# QTPY_v3.net
KiCad netlist of a schematic drawn in EAGLE
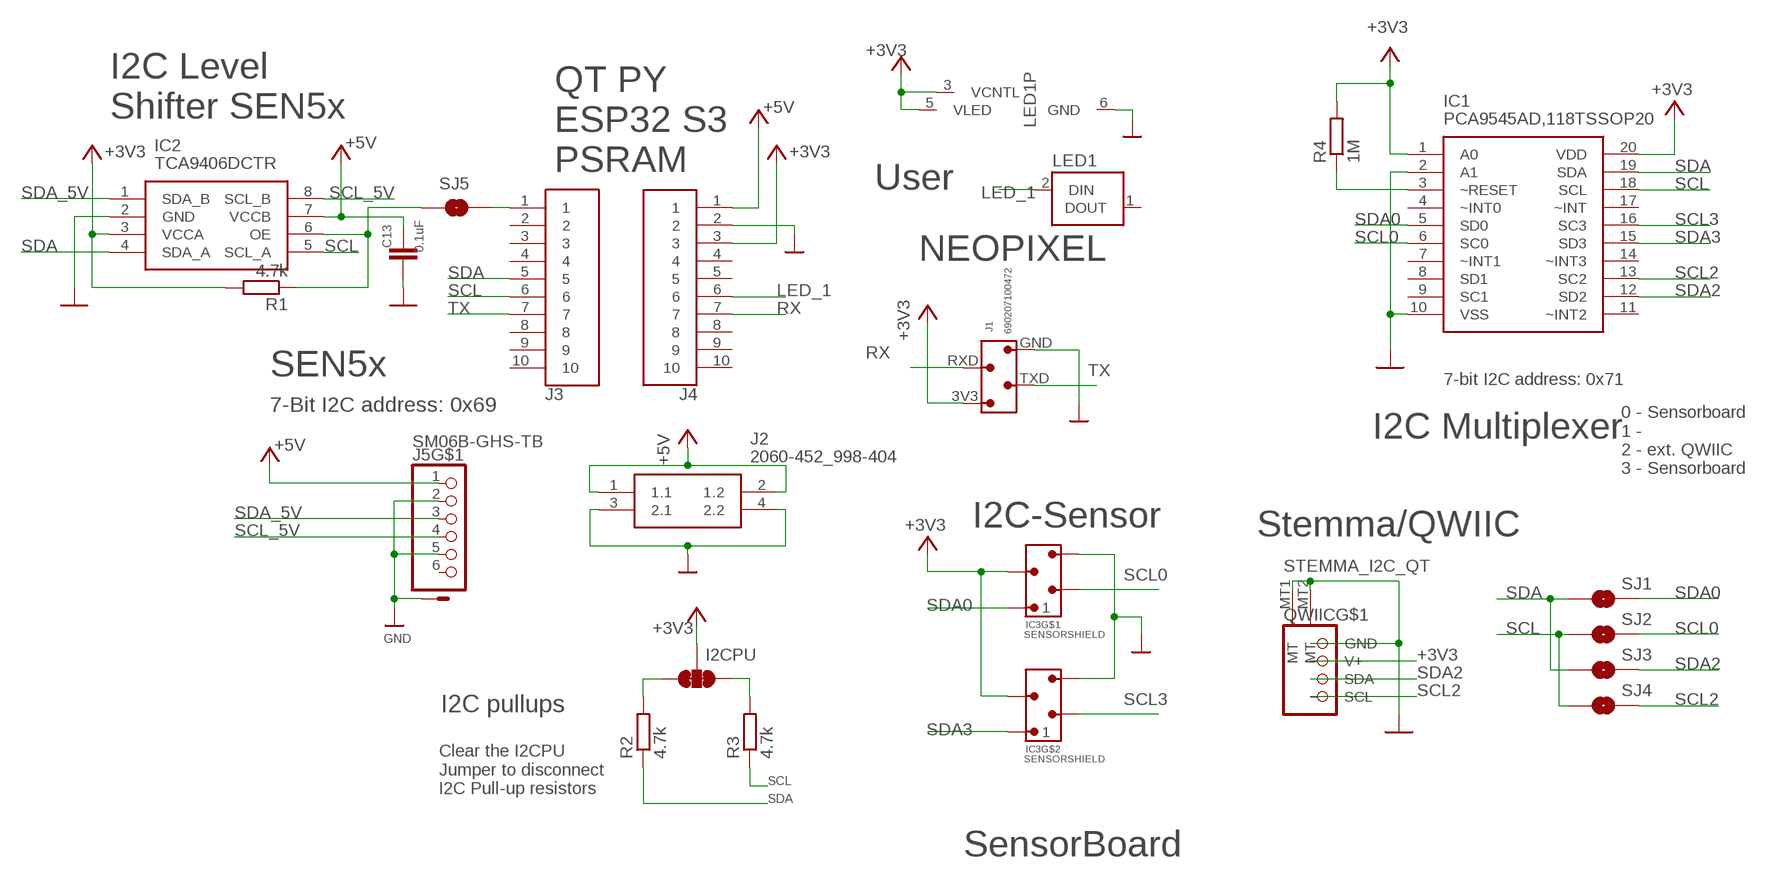
[diagram p0: schematic, sheet 1]

(export (version "E")
  (design (tool "Eeschema 10.0.6"))
  (components
    (comp (ref "C13")
      (value "0.1uF")
      (footprint "eagle-import:C0603")
      (libsource (lib "eagle-import") (part "C-EUC0603"))
    )
    (comp (ref "I2CPU")
      (value "I2C PU")
      (footprint "eagle-import:SMT-JUMPER_3_2-NC_TRACE_SILK")
      (libsource (lib "eagle-import") (part "JUMPER-SMT_3_2-NC_TRACE_SILK"))
    )
    (comp (ref "IC1")
      (value "PCA9545AD,118TSSOP20")
      (footprint "eagle-import:TSSOP20")
      (libsource (lib "eagle-import") (part "PCA9545AD,118TSSOP20"))
    )
    (comp (ref "IC2")
      (value "TCA9406DCTR")
      (footprint "eagle-import:SOP65P400X130-8N")
      (fields (field (name "MOUSER_PART_NUMBER") "595-TCA9406DCTR"))
      (libsource (lib "eagle-import") (part "TCA9406DCTR"))
    )
    (comp (ref "IC3")
      (value "SENSORSHIELD")
      (footprint "eagle-import:SENSORSHIELD")
      (libsource (lib "eagle-import") (part "SENSORSHIELD"))
    )
    (comp (ref "J1")
      (value "690207100472")
      (footprint "eagle-import:LORASHIELD")
      (libsource (lib "eagle-import") (part "LORASHIELD"))
    )
    (comp (ref "J2")
      (value "2060-452_998-404")
      (footprint "eagle-import:2060452998404")
      (fields (field (name "ARROW_PART_NUMBER") "2060-452/998-404"))
      (libsource (lib "eagle-import") (part "2060-452_998-404"))
    )
    (comp (ref "J3")
      (value "BG125-10-A-1-1-0440-N-D")
      (footprint "eagle-import:BG12510A110440ND")
      (fields (field (name "MOUSER_PART_NUMBER") "640-BG12510A110440ND"))
      (libsource (lib "eagle-import") (part "BG125-10-A-1-1-0440-N-D"))
    )
    (comp (ref "J4")
      (value "BG125-10-A-1-1-0440-N-D")
      (footprint "eagle-import:BG12510A110440ND")
      (fields (field (name "MOUSER_PART_NUMBER") "640-BG12510A110440ND"))
      (libsource (lib "eagle-import") (part "BG125-10-A-1-1-0440-N-D"))
    )
    (comp (ref "J5")
      (value "SM06B-GHS-TB")
      (footprint "eagle-import:JST-PH-06-SMD")
      (libsource (lib "eagle-import") (part "JST-PH-06-SMDSMD"))
    )
    (comp (ref "LED1")
      (value "WS2812WS2812")
      (footprint "eagle-import:WS2812")
      (libsource (lib "eagle-import") (part "WS2812WS2812"))
    )
    (comp (ref "QWIIC")
      (value "STEMMA_I2C_QT")
      (footprint "eagle-import:JST_SH4")
      (libsource (lib "eagle-import") (part "STEMMA_I2C_QT"))
    )
    (comp (ref "R1")
      (value "4.7k")
      (footprint "eagle-import:R0603")
      (libsource (lib "eagle-import") (part "R-EU_R0603"))
    )
    (comp (ref "R2")
      (value "4.7k")
      (footprint "eagle-import:R0603")
      (libsource (lib "eagle-import") (part "R-EU_R0603"))
    )
    (comp (ref "R3")
      (value "4.7k")
      (footprint "eagle-import:R0603")
      (libsource (lib "eagle-import") (part "R-EU_R0603"))
    )
    (comp (ref "R4")
      (value "1M")
      (footprint "eagle-import:R0603")
      (libsource (lib "eagle-import") (part "R-EU_R0603"))
    )
    (comp (ref "SJ1")
      (value "SOLDERJUMPERNO")
      (footprint "eagle-import:SJ_2S-NO")
      (libsource (lib "eagle-import") (part "SOLDERJUMPERNO"))
    )
    (comp (ref "SJ2")
      (value "SOLDERJUMPERNO")
      (footprint "eagle-import:SJ_2S-NO")
      (libsource (lib "eagle-import") (part "SOLDERJUMPERNO"))
    )
    (comp (ref "SJ3")
      (value "SOLDERJUMPERNO")
      (footprint "eagle-import:SJ_2S-NO")
      (libsource (lib "eagle-import") (part "SOLDERJUMPERNO"))
    )
    (comp (ref "SJ4")
      (value "SOLDERJUMPERNO")
      (footprint "eagle-import:SJ_2S-NO")
      (libsource (lib "eagle-import") (part "SOLDERJUMPERNO"))
    )
    (comp (ref "SJ5")
      (value "SOLDERJUMPERNO")
      (footprint "eagle-import:SJ_2S-NO")
      (libsource (lib "eagle-import") (part "SOLDERJUMPERNO"))
    )
  )
  (nets
    (net (code "1") (name "+3V3") (class "Default")
      (node (ref "I2CPU") (pin "2") (pinfunction "2_2") (pintype "passive"))
      (node (ref "IC1") (pin "1") (pinfunction "A0_1") (pintype "bidirectional"))
      (node (ref "IC1") (pin "20") (pinfunction "VDD_20") (pintype "bidirectional"))
      (node (ref "IC2") (pin "3") (pinfunction "VCCA_3") (pintype "bidirectional"))
      (node (ref "IC3") (pin "3V3_1") (pinfunction "3_3V3_1") (pintype "passive"))
      (node (ref "IC3") (pin "3V3_2") (pinfunction "3_3V3_2") (pintype "passive"))
      (node (ref "J1") (pin "3V3") (pinfunction "4_3V3") (pintype "passive"))
      (node (ref "J3") (pin "3") (pinfunction "3_3") (pintype "bidirectional"))
      (node (ref "LED1") (pin "3") (pinfunction "VCNTL_3") (pintype "power_in"))
      (node (ref "LED1") (pin "5") (pinfunction "VLED_5") (pintype "power_in"))
      (node (ref "QWIIC") (pin "2") (pinfunction "V+_2") (pintype "passive"))
      (node (ref "R1") (pin "2") (pinfunction "2_2") (pintype "passive"))
      (node (ref "R4") (pin "2") (pinfunction "2_2") (pintype "passive"))
    )
    (net (code "2") (name "+5V") (class "Default")
      (node (ref "C13") (pin "1") (pinfunction "1_1") (pintype "passive"))
      (node (ref "IC2") (pin "7") (pinfunction "VCCB_7") (pintype "bidirectional"))
      (node (ref "J2") (pin "1") (pinfunction "1.1_1") (pintype "bidirectional"))
      (node (ref "J2") (pin "2") (pinfunction "1.2_2") (pintype "bidirectional"))
      (node (ref "J3") (pin "1") (pinfunction "1_1") (pintype "bidirectional"))
      (node (ref "J5") (pin "1") (pinfunction "1_1") (pintype "passive"))
    )
    (net (code "3") (name "/LED_1") (class "Default")
      (node (ref "J3") (pin "6") (pinfunction "6_6") (pintype "bidirectional"))
      (node (ref "LED1") (pin "2") (pinfunction "DIN_2") (pintype "input"))
    )
    (net (code "4") (name "/SCL_5V") (class "Default")
      (node (ref "IC2") (pin "8") (pinfunction "SCL_B_8") (pintype "bidirectional"))
      (node (ref "J5") (pin "4") (pinfunction "4_4") (pintype "passive"))
    )
    (net (code "5") (name "/SDA_5V") (class "Default")
      (node (ref "IC2") (pin "1") (pinfunction "SDA_B_1") (pintype "bidirectional"))
      (node (ref "J5") (pin "3") (pinfunction "3_3") (pintype "passive"))
    )
    (net (code "6") (name "GND") (class "Default")
      (node (ref "C13") (pin "2") (pinfunction "2_2") (pintype "passive"))
      (node (ref "IC1") (pin "10") (pinfunction "VSS_10") (pintype "bidirectional"))
      (node (ref "IC1") (pin "2") (pinfunction "A1_2") (pintype "bidirectional"))
      (node (ref "IC2") (pin "2") (pinfunction "GND_2") (pintype "bidirectional"))
      (node (ref "IC3") (pin "GND_1") (pinfunction "4_GND_1") (pintype "passive"))
      (node (ref "IC3") (pin "GND_2") (pinfunction "4_GND_2") (pintype "passive"))
      (node (ref "J1") (pin "GND") (pinfunction "1_GND") (pintype "passive"))
      (node (ref "J2") (pin "3") (pinfunction "2.1_3") (pintype "bidirectional"))
      (node (ref "J2") (pin "4") (pinfunction "2.2_4") (pintype "bidirectional"))
      (node (ref "J3") (pin "2") (pinfunction "2_2") (pintype "bidirectional"))
      (node (ref "J5") (pin "2") (pinfunction "2_2") (pintype "passive"))
      (node (ref "J5") (pin "5") (pinfunction "5_5") (pintype "passive"))
      (node (ref "J5") (pin "7") (pinfunction "S_7") (pintype "passive"))
      (node (ref "J5") (pin "8") (pinfunction "S_8") (pintype "passive"))
      (node (ref "LED1") (pin "6") (pinfunction "GND_6") (pintype "power_in"))
      (node (ref "QWIIC") (pin "1") (pinfunction "GND_1") (pintype "passive"))
      (node (ref "QWIIC") (pin "MT1") (pinfunction "MT_MT1") (pintype "bidirectional"))
      (node (ref "QWIIC") (pin "MT2") (pinfunction "MT_MT2") (pintype "bidirectional"))
    )
    (net (code "7") (name "Net-(I2CPU-Pad1)") (class "Default")
      (node (ref "I2CPU") (pin "1") (pinfunction "1_1") (pintype "passive"))
      (node (ref "R3") (pin "2") (pinfunction "2_2") (pintype "passive"))
    )
    (net (code "8") (name "Net-(I2CPU-Pad3)") (class "Default")
      (node (ref "I2CPU") (pin "3") (pinfunction "3_3") (pintype "passive"))
      (node (ref "R2") (pin "2") (pinfunction "2_2") (pintype "passive"))
    )
    (net (code "9") (name "Net-(IC1-~{RESET})") (class "Default")
      (node (ref "IC1") (pin "3") (pinfunction "~{RESET}_3") (pintype "bidirectional"))
      (node (ref "R4") (pin "1") (pinfunction "1_1") (pintype "passive"))
    )
    (net (code "10") (name "Net-(IC2-OE)") (class "Default")
      (node (ref "IC2") (pin "6") (pinfunction "OE_6") (pintype "bidirectional"))
      (node (ref "R1") (pin "1") (pinfunction "1_1") (pintype "passive"))
      (node (ref "SJ5") (pin "1") (pinfunction "1_1") (pintype "passive"))
    )
    (net (code "11") (name "Net-(J4-Pad1)") (class "Default")
      (node (ref "J4") (pin "1") (pinfunction "1_1") (pintype "bidirectional"))
      (node (ref "SJ5") (pin "2") (pinfunction "2_2") (pintype "passive"))
    )
    (net (code "12") (name "RX") (class "Default")
      (node (ref "J1") (pin "RXD") (pinfunction "2_RXD") (pintype "passive"))
      (node (ref "J3") (pin "7") (pinfunction "7_7") (pintype "bidirectional"))
    )
    (net (code "13") (name "SCL") (class "Default")
      (node (ref "IC1") (pin "18") (pinfunction "SCL_18") (pintype "bidirectional"))
      (node (ref "IC2") (pin "5") (pinfunction "SCL_A_5") (pintype "bidirectional"))
      (node (ref "J4") (pin "6") (pinfunction "6_6") (pintype "bidirectional"))
      (node (ref "R3") (pin "1") (pinfunction "1_1") (pintype "passive"))
      (node (ref "SJ2") (pin "1") (pinfunction "1_1") (pintype "passive"))
      (node (ref "SJ4") (pin "1") (pinfunction "1_1") (pintype "passive"))
    )
    (net (code "14") (name "SCL0") (class "Default")
      (node (ref "IC1") (pin "6") (pinfunction "SC0_6") (pintype "bidirectional"))
      (node (ref "IC3") (pin "SCL0") (pinfunction "2_SCL0") (pintype "passive"))
      (node (ref "SJ2") (pin "2") (pinfunction "2_2") (pintype "passive"))
    )
    (net (code "15") (name "SCL2") (class "Default")
      (node (ref "IC1") (pin "13") (pinfunction "SC2_13") (pintype "bidirectional"))
      (node (ref "QWIIC") (pin "4") (pinfunction "SCL_4") (pintype "passive"))
      (node (ref "SJ4") (pin "2") (pinfunction "2_2") (pintype "passive"))
    )
    (net (code "16") (name "SCL3") (class "Default")
      (node (ref "IC1") (pin "16") (pinfunction "SC3_16") (pintype "bidirectional"))
      (node (ref "IC3") (pin "SCL1") (pinfunction "2_SCL1") (pintype "passive"))
    )
    (net (code "17") (name "SDA") (class "Default")
      (node (ref "IC1") (pin "19") (pinfunction "SDA_19") (pintype "bidirectional"))
      (node (ref "IC2") (pin "4") (pinfunction "SDA_A_4") (pintype "bidirectional"))
      (node (ref "J4") (pin "5") (pinfunction "5_5") (pintype "bidirectional"))
      (node (ref "R2") (pin "1") (pinfunction "1_1") (pintype "passive"))
      (node (ref "SJ1") (pin "1") (pinfunction "1_1") (pintype "passive"))
      (node (ref "SJ3") (pin "1") (pinfunction "1_1") (pintype "passive"))
    )
    (net (code "18") (name "SDA0") (class "Default")
      (node (ref "IC1") (pin "5") (pinfunction "SD0_5") (pintype "bidirectional"))
      (node (ref "IC3") (pin "SDA0") (pinfunction "1_SDA0") (pintype "passive"))
      (node (ref "SJ1") (pin "2") (pinfunction "2_2") (pintype "passive"))
    )
    (net (code "19") (name "SDA2") (class "Default")
      (node (ref "IC1") (pin "12") (pinfunction "SD2_12") (pintype "bidirectional"))
      (node (ref "QWIIC") (pin "3") (pinfunction "SDA_3") (pintype "passive"))
      (node (ref "SJ3") (pin "2") (pinfunction "2_2") (pintype "passive"))
    )
    (net (code "20") (name "SDA3") (class "Default")
      (node (ref "IC1") (pin "15") (pinfunction "SD3_15") (pintype "bidirectional"))
      (node (ref "IC3") (pin "SDA1") (pinfunction "1_SDA1") (pintype "passive"))
    )
    (net (code "21") (name "TX") (class "Default")
      (node (ref "J1") (pin "TXD") (pinfunction "3_TXD") (pintype "passive"))
      (node (ref "J4") (pin "7") (pinfunction "7_7") (pintype "bidirectional"))
    )
    (net (code "22") (name "unconnected-(IC1-SC1-Pad9)") (class "Default")
      (node (ref "IC1") (pin "9") (pinfunction "SC1_9") (pintype "bidirectional"))
    )
    (net (code "23") (name "unconnected-(IC1-SD1-Pad8)") (class "Default")
      (node (ref "IC1") (pin "8") (pinfunction "SD1_8") (pintype "bidirectional"))
    )
    (net (code "24") (name "unconnected-(IC1-~{INT0}-Pad4)") (class "Default")
      (node (ref "IC1") (pin "4") (pinfunction "~{INT0}_4") (pintype "bidirectional"))
    )
    (net (code "25") (name "unconnected-(IC1-~{INT1}-Pad7)") (class "Default")
      (node (ref "IC1") (pin "7") (pinfunction "~{INT1}_7") (pintype "bidirectional"))
    )
    (net (code "26") (name "unconnected-(IC1-~{INT2}-Pad11)") (class "Default")
      (node (ref "IC1") (pin "11") (pinfunction "~{INT2}_11") (pintype "bidirectional"))
    )
    (net (code "27") (name "unconnected-(IC1-~{INT3}-Pad14)") (class "Default")
      (node (ref "IC1") (pin "14") (pinfunction "~{INT3}_14") (pintype "bidirectional"))
    )
    (net (code "28") (name "unconnected-(IC1-~{INT}-Pad17)") (class "Default")
      (node (ref "IC1") (pin "17") (pinfunction "~{INT}_17") (pintype "bidirectional"))
    )
    (net (code "29") (name "unconnected-(J3-Pad4)") (class "Default")
      (node (ref "J3") (pin "4") (pinfunction "4_4") (pintype "bidirectional"))
    )
    (net (code "30") (name "unconnected-(J3-Pad5)") (class "Default")
      (node (ref "J3") (pin "5") (pinfunction "5_5") (pintype "bidirectional"))
    )
    (net (code "31") (name "unconnected-(J3-Pad8)") (class "Default")
      (node (ref "J3") (pin "8") (pinfunction "8_8") (pintype "bidirectional"))
    )
    (net (code "32") (name "unconnected-(J3-Pad9)") (class "Default")
      (node (ref "J3") (pin "9") (pinfunction "9_9") (pintype "bidirectional"))
    )
    (net (code "33") (name "unconnected-(J3-Pad10)") (class "Default")
      (node (ref "J3") (pin "10") (pinfunction "10_10") (pintype "bidirectional"))
    )
    (net (code "34") (name "unconnected-(J4-Pad2)") (class "Default")
      (node (ref "J4") (pin "2") (pinfunction "2_2") (pintype "bidirectional"))
    )
    (net (code "35") (name "unconnected-(J4-Pad3)") (class "Default")
      (node (ref "J4") (pin "3") (pinfunction "3_3") (pintype "bidirectional"))
    )
    (net (code "36") (name "unconnected-(J4-Pad4)") (class "Default")
      (node (ref "J4") (pin "4") (pinfunction "4_4") (pintype "bidirectional"))
    )
    (net (code "37") (name "unconnected-(J4-Pad8)") (class "Default")
      (node (ref "J4") (pin "8") (pinfunction "8_8") (pintype "bidirectional"))
    )
    (net (code "38") (name "unconnected-(J4-Pad9)") (class "Default")
      (node (ref "J4") (pin "9") (pinfunction "9_9") (pintype "bidirectional"))
    )
    (net (code "39") (name "unconnected-(J4-Pad10)") (class "Default")
      (node (ref "J4") (pin "10") (pinfunction "10_10") (pintype "bidirectional"))
    )
    (net (code "40") (name "unconnected-(J5-Pad6)") (class "Default")
      (node (ref "J5") (pin "6") (pinfunction "6_6") (pintype "passive"))
    )
    (net (code "41") (name "unconnected-(LED1B-DOUT-Pad1)") (class "Default")
      (node (ref "LED1") (pin "1") (pinfunction "DOUT_1") (pintype "output"))
    )
  )
)
